# ESP32-with-USB.net
KiCad netlist of a schematic drawn in Altium Designer
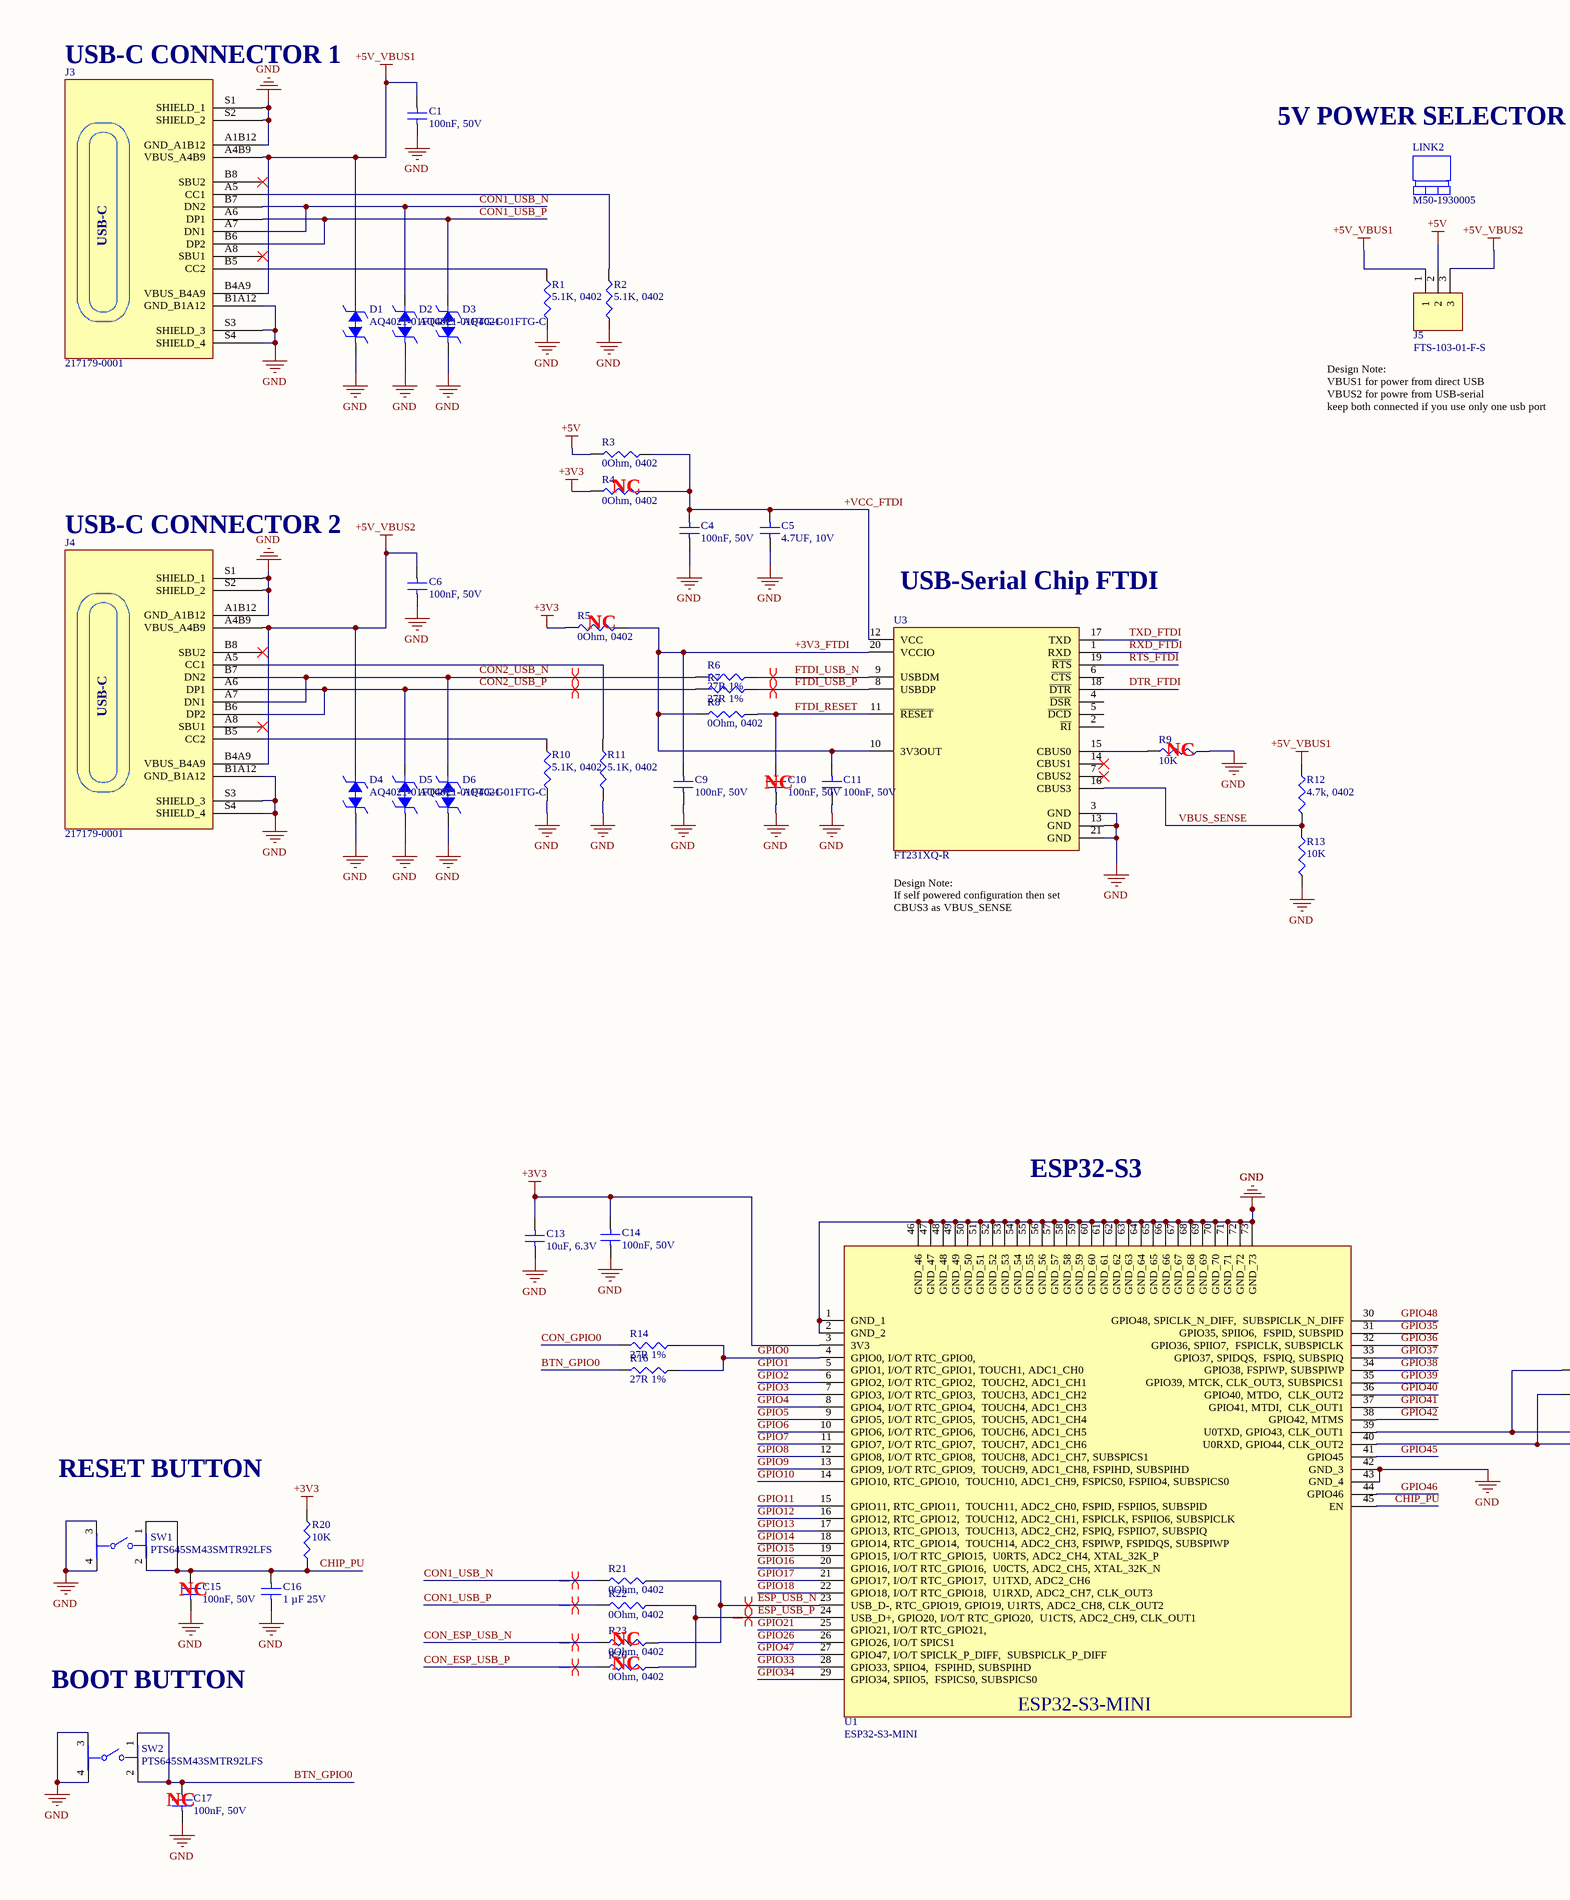
[diagram p0: ESP32-with-USB.SchDoc, left]
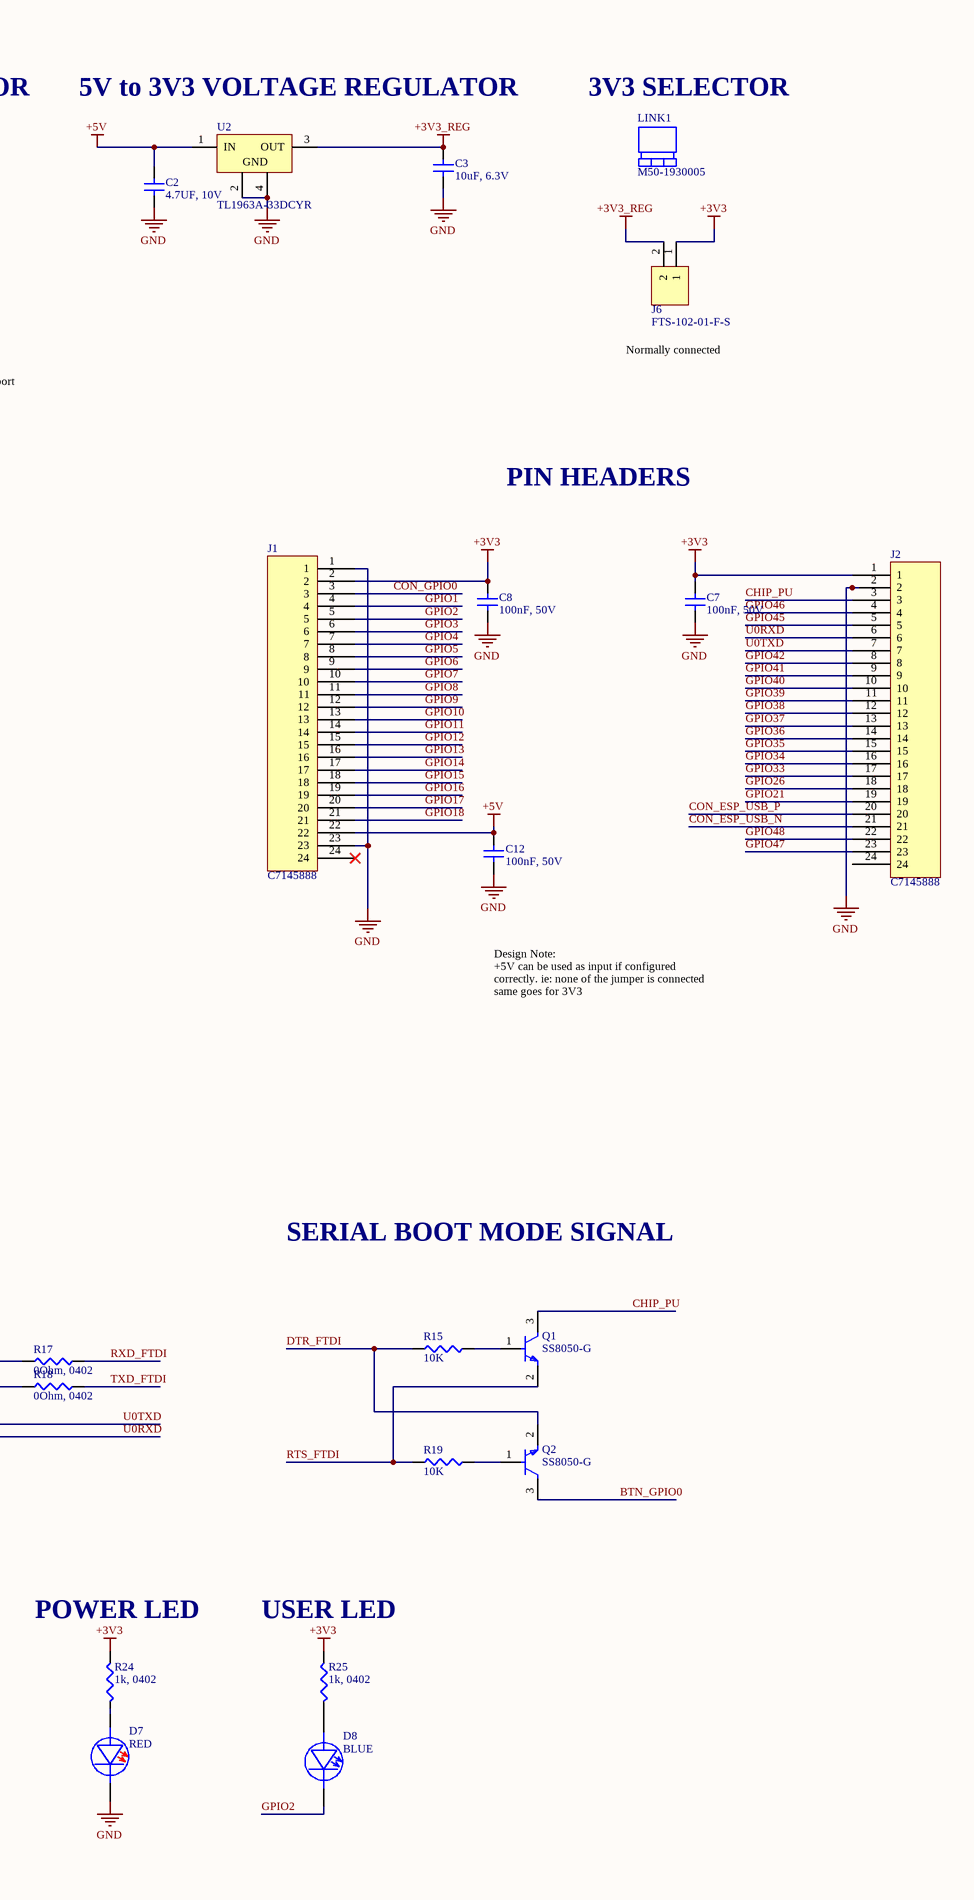
[diagram p1: ESP32-with-USB.SchDoc, right]

(export (version "E")
  (design (tool "Eeschema 10.0.6"))
  (components
    (comp (ref "C1")
      (value "100nF, 50V")
      (footprint "CAPC1005X55N")
      (description "0.1 µF ±10% 50V Ceramic Capacitor X7R 0402 (1005 Metric)")
      (fields
        (field (name "MANUFACTURER") "Samsung")
        (field (name "MANUFACTURER PART NUMBER") "CL05B104KB54PNC")
      )
      (libsource (lib "Schlib") (part "CL05B104KB54PNC"))
    )
    (comp (ref "C2")
      (value "4.7UF, 10V")
      (footprint "CAPC1005X55N")
      (description "CAP CER 4.7UF 10V X5R 0402")
      (fields
        (field (name "MANUFACTURER") "Samsung")
        (field (name "MANUFACTURER PART NUMBER") "CL05A475MP5NRNC")
      )
      (libsource (lib "Schlib") (part "CL05A475MP5NRNC"))
    )
    (comp (ref "C3")
      (value "10uF, 6.3V")
      (footprint "CAPC1005X55N")
      (description "10 µF ±20% 6.3V Ceramic Capacitor X5R 0402 (1005 Metric)")
      (fields
        (field (name "MANUFACTURER") "Murata")
        (field (name "MANUFACTURER PART NUMBER") "GRM155R60J106ME05D")
      )
      (libsource (lib "Schlib") (part "GRM155R60J106ME05D"))
    )
    (comp (ref "C4")
      (value "100nF, 50V")
      (footprint "CAPC1005X55N")
      (description "0.1 µF ±10% 50V Ceramic Capacitor X7R 0402 (1005 Metric)")
      (fields
        (field (name "MANUFACTURER") "Samsung")
        (field (name "MANUFACTURER PART NUMBER") "CL05B104KB54PNC")
      )
      (libsource (lib "Schlib") (part "CL05B104KB54PNC"))
    )
    (comp (ref "C5")
      (value "4.7UF, 10V")
      (footprint "CAPC1005X55N")
      (description "CAP CER 4.7UF 10V X5R 0402")
      (fields
        (field (name "MANUFACTURER") "Samsung")
        (field (name "MANUFACTURER PART NUMBER") "CL05A475MP5NRNC")
      )
      (libsource (lib "Schlib") (part "CL05A475MP5NRNC"))
    )
    (comp (ref "C6")
      (value "100nF, 50V")
      (footprint "CAPC1005X55N")
      (description "0.1 µF ±10% 50V Ceramic Capacitor X7R 0402 (1005 Metric)")
      (fields
        (field (name "MANUFACTURER") "Samsung")
        (field (name "MANUFACTURER PART NUMBER") "CL05B104KB54PNC")
      )
      (libsource (lib "Schlib") (part "CL05B104KB54PNC"))
    )
    (comp (ref "C7")
      (value "100nF, 50V")
      (footprint "CAPC1005X55N")
      (description "0.1 µF ±10% 50V Ceramic Capacitor X7R 0402 (1005 Metric)")
      (fields
        (field (name "MANUFACTURER") "Samsung")
        (field (name "MANUFACTURER PART NUMBER") "CL05B104KB54PNC")
      )
      (libsource (lib "Schlib") (part "CL05B104KB54PNC"))
    )
    (comp (ref "C8")
      (value "100nF, 50V")
      (footprint "CAPC1005X55N")
      (description "0.1 µF ±10% 50V Ceramic Capacitor X7R 0402 (1005 Metric)")
      (fields
        (field (name "MANUFACTURER") "Samsung")
        (field (name "MANUFACTURER PART NUMBER") "CL05B104KB54PNC")
      )
      (libsource (lib "Schlib") (part "CL05B104KB54PNC"))
    )
    (comp (ref "C9")
      (value "100nF, 50V")
      (footprint "CAPC1005X55N")
      (description "0.1 µF ±10% 50V Ceramic Capacitor X7R 0402 (1005 Metric)")
      (fields
        (field (name "MANUFACTURER") "Samsung")
        (field (name "MANUFACTURER PART NUMBER") "CL05B104KB54PNC")
      )
      (libsource (lib "Schlib") (part "CL05B104KB54PNC"))
    )
    (comp (ref "C10")
      (value "100nF, 50V")
      (footprint "CAPC1005X55N")
      (description "0.1 µF ±10% 50V Ceramic Capacitor X7R 0402 (1005 Metric)")
      (fields
        (field (name "MANUFACTURER") "Samsung")
        (field (name "MANUFACTURER PART NUMBER") "CL05B104KB54PNC")
      )
      (libsource (lib "Schlib") (part "CL05B104KB54PNC"))
    )
    (comp (ref "C11")
      (value "100nF, 50V")
      (footprint "CAPC1005X55N")
      (description "0.1 µF ±10% 50V Ceramic Capacitor X7R 0402 (1005 Metric)")
      (fields
        (field (name "MANUFACTURER") "Samsung")
        (field (name "MANUFACTURER PART NUMBER") "CL05B104KB54PNC")
      )
      (libsource (lib "Schlib") (part "CL05B104KB54PNC"))
    )
    (comp (ref "C12")
      (value "100nF, 50V")
      (footprint "CAPC1005X55N")
      (description "0.1 µF ±10% 50V Ceramic Capacitor X7R 0402 (1005 Metric)")
      (fields
        (field (name "MANUFACTURER") "Samsung")
        (field (name "MANUFACTURER PART NUMBER") "CL05B104KB54PNC")
      )
      (libsource (lib "Schlib") (part "CL05B104KB54PNC"))
    )
    (comp (ref "C13")
      (value "10uF, 6.3V")
      (footprint "CAPC1005X55N")
      (description "10 µF ±20% 6.3V Ceramic Capacitor X5R 0402 (1005 Metric)")
      (fields
        (field (name "MANUFACTURER") "Murata")
        (field (name "MANUFACTURER PART NUMBER") "GRM155R60J106ME05D")
      )
      (libsource (lib "Schlib") (part "GRM155R60J106ME05D"))
    )
    (comp (ref "C14")
      (value "100nF, 50V")
      (footprint "CAPC1005X55N")
      (description "0.1 µF ±10% 50V Ceramic Capacitor X7R 0402 (1005 Metric)")
      (fields
        (field (name "MANUFACTURER") "Samsung")
        (field (name "MANUFACTURER PART NUMBER") "CL05B104KB54PNC")
      )
      (libsource (lib "Schlib") (part "CL05B104KB54PNC"))
    )
    (comp (ref "C15")
      (value "100nF, 50V")
      (footprint "CAPC1005X55N")
      (description "0.1 µF ±10% 50V Ceramic Capacitor X7R 0402 (1005 Metric)")
      (fields
        (field (name "MANUFACTURER") "Samsung")
        (field (name "MANUFACTURER PART NUMBER") "CL05B104KB54PNC")
      )
      (libsource (lib "Schlib") (part "CL05B104KB54PNC"))
    )
    (comp (ref "C16")
      (value "1 µF 25V")
      (footprint "CAPC1005X55N")
      (description "1 µF ±10% 25V Ceramic Capacitor X5R 0402 (1005 Metric)")
      (fields
        (field (name "MANUFACTURER") "Samsung")
        (field (name "MANUFACTURER PART NUMBER") "CL05A105KA5NQNC")
      )
      (libsource (lib "Schlib") (part "CL05A105KA5NQNC"))
    )
    (comp (ref "C17")
      (value "100nF, 50V")
      (footprint "CAPC1005X55N")
      (description "0.1 µF ±10% 50V Ceramic Capacitor X7R 0402 (1005 Metric)")
      (fields
        (field (name "MANUFACTURER") "Samsung")
        (field (name "MANUFACTURER PART NUMBER") "CL05B104KB54PNC")
      )
      (libsource (lib "Schlib") (part "CL05B104KB54PNC"))
    )
    (comp (ref "D1")
      (value "AQ4021-01FTG-C")
      (footprint "AQ4021-01FTG-C_0805")
      (description "Trans Voltage Suppressor Diode")
      (fields (field (name "MANUFACTURER") "Littelfuse") (field (name "LCSC PART NUMBER") "C708873"))
      (libsource (lib "Schlib") (part "AQ4021-01FTG-C"))
    )
    (comp (ref "D2")
      (value "AQ4021-01FTG-C")
      (footprint "AQ4021-01FTG-C_0805")
      (description "Trans Voltage Suppressor Diode")
      (fields (field (name "MANUFACTURER") "Littelfuse") (field (name "LCSC PART NUMBER") "C708873"))
      (libsource (lib "Schlib") (part "AQ4021-01FTG-C"))
    )
    (comp (ref "D3")
      (value "AQ4021-01FTG-C")
      (footprint "AQ4021-01FTG-C_0805")
      (description "Trans Voltage Suppressor Diode")
      (fields (field (name "MANUFACTURER") "Littelfuse") (field (name "LCSC PART NUMBER") "C708873"))
      (libsource (lib "Schlib") (part "AQ4021-01FTG-C"))
    )
    (comp (ref "D4")
      (value "AQ4021-01FTG-C")
      (footprint "AQ4021-01FTG-C_0805")
      (description "Trans Voltage Suppressor Diode")
      (fields (field (name "MANUFACTURER") "Littelfuse") (field (name "LCSC PART NUMBER") "C708873"))
      (libsource (lib "Schlib") (part "AQ4021-01FTG-C"))
    )
    (comp (ref "D5")
      (value "AQ4021-01FTG-C")
      (footprint "AQ4021-01FTG-C_0805")
      (description "Trans Voltage Suppressor Diode")
      (fields (field (name "MANUFACTURER") "Littelfuse") (field (name "LCSC PART NUMBER") "C708873"))
      (libsource (lib "Schlib") (part "AQ4021-01FTG-C"))
    )
    (comp (ref "D6")
      (value "AQ4021-01FTG-C")
      (footprint "AQ4021-01FTG-C_0805")
      (description "Trans Voltage Suppressor Diode")
      (fields (field (name "MANUFACTURER") "Littelfuse") (field (name "LCSC PART NUMBER") "C708873"))
      (libsource (lib "Schlib") (part "AQ4021-01FTG-C"))
    )
    (comp (ref "D7")
      (value "RED")
      (footprint "LED_RED_0402")
      (description "LED RED 0402 SMD")
      (fields
        (field (name "MANUFACTURER") "Vishay")
        (field (name "MANUFACTURER PART NUMBER") "VLMS1500-GS08")
      )
      (libsource (lib "Schlib") (part "VLMS1500-GS08"))
    )
    (comp (ref "D8")
      (value "BLUE")
      (footprint "LED_BLUE_0402")
      (description "LED BLUE 0402 SMD 468nm")
      (fields
        (field (name "MANUFACTURER") "Vishay")
        (field (name "MANUFACTURER PART NUMBER") "VLMB1500-GS08")
      )
      (libsource (lib "Schlib") (part "VLMB1500-GS08"))
    )
    (comp (ref "J1")
      (value "C7145888")
      (footprint "HDR_1X24_2.54MM")
      (description "CONN HEADER VERT 24POS 2.54MM")
      (fields (field (name "MANUFACTURER") "Molex") (field (name "MANUFACTURER PART NUMBER") "0022284245"))
      (libsource (lib "Schlib") (part "0022284245"))
    )
    (comp (ref "J2")
      (value "C7145888")
      (footprint "HDR_1X24_2.54MM")
      (description "CONN HEADER VERT 24POS 2.54MM")
      (fields (field (name "MANUFACTURER") "Molex") (field (name "MANUFACTURER PART NUMBER") "0022284245"))
      (libsource (lib "") (part "0022284245_1"))
    )
    (comp (ref "J3")
      (value "217179-0001")
      (footprint "FP-2171790001-MFG")
      (description "USB Type C - Connector, Top-mount SMT, 16pos ¦ Molex Incorporated 217179-0001")
      (fields (field (name "MANUFACTURER") "Molex") (field (name "LCSC PART NUMBER") "C3197684"))
      (libsource (lib "Schlib") (part "217179-0001"))
    )
    (comp (ref "J4")
      (value "217179-0001")
      (footprint "FP-2171790001-MFG")
      (description "USB Type C - Connector, Top-mount SMT, 16pos ¦ Molex Incorporated 217179-0001")
      (fields (field (name "MANUFACTURER") "Molex") (field (name "LCSC PART NUMBER") "C3197684"))
      (libsource (lib "Schlib") (part "217179-0001"))
    )
    (comp (ref "J5")
      (value "FTS-103-01-F-S")
      (footprint "HDR_1X3_1.27MM")
      (description "CONN HEADER VERT 3POS 1.27MM")
      (fields (field (name "MANUFACTURER") "Samtec") (field (name "LCSC PART NUMBER") "C3333578"))
      (libsource (lib "Schlib") (part "FTS-103-01-F-S"))
    )
    (comp (ref "J6")
      (value "FTS-102-01-F-S")
      (footprint "HDR_1X2_1.27MM")
      (description "CONN HEADER VERT 2POS 1.27MM")
      (fields (field (name "MANUFACTURER") "Samtec") (field (name "LCSC PART NUMBER") "C6045317"))
      (libsource (lib "Schlib") (part "FTS-102-01-F-S"))
    )
    (comp (ref "LINK1")
      (value "M50-1930005")
      (description "CONN SHUNT 1.27MM BLUE")
      (fields (field (name "MANUFACTURER") "Harwin") (field (name "LCSC PART NUMBER") "C6586863"))
      (libsource (lib "Schlib") (part "M50-1930005"))
    )
    (comp (ref "LINK2")
      (value "M50-1930005")
      (description "CONN SHUNT 1.27MM BLUE")
      (fields (field (name "MANUFACTURER") "Harwin") (field (name "LCSC PART NUMBER") "C6586863"))
      (libsource (lib "Schlib") (part "M50-1930005"))
    )
    (comp (ref "Q1")
      (value "SS8050-G")
      (footprint "FP-SS8050-G-IPC_B")
      (description "TRANS NPN 25V 1.5A SOT23-3")
      (fields (field (name "MANUFACTURER") "Comchip") (field (name "LCSC PART NUMBER") "C164886"))
      (libsource (lib "Schlib") (part "SS8050-G"))
    )
    (comp (ref "Q2")
      (value "SS8050-G")
      (footprint "FP-SS8050-G-IPC_B")
      (description "TRANS NPN 25V 1.5A SOT23-3")
      (fields (field (name "MANUFACTURER") "Comchip") (field (name "LCSC PART NUMBER") "C164886"))
      (libsource (lib "Schlib") (part "SS8050-G"))
    )
    (comp (ref "R1")
      (value "5.1K, 0402")
      (footprint "RESC1005X37N")
      (description "5.1kOhm 1% 1/16W 0402")
      (fields
        (field (name "MANUFACTURER") "Yageo")
        (field (name "MANUFACTURER PART NUMBER") "RC0402FR-075K1L")
      )
      (libsource (lib "Schlib") (part "RC0402FR-075K1L"))
    )
    (comp (ref "R2")
      (value "5.1K, 0402")
      (footprint "RESC1005X37N")
      (description "5.1kOhm 1% 1/16W 0402")
      (fields
        (field (name "MANUFACTURER") "Yageo")
        (field (name "MANUFACTURER PART NUMBER") "RC0402FR-075K1L")
      )
      (libsource (lib "Schlib") (part "RC0402FR-075K1L"))
    )
    (comp (ref "R3")
      (value "0Ohm, 0402")
      (footprint "RESC1005X37N")
      (description "RES 0 OHM JUMPER 1/16W 0402")
      (fields
        (field (name "MANUFACTURER") "Yageo")
        (field (name "MANUFACTURER PART NUMBER") "RC0402JR-070RL")
      )
      (libsource (lib "Schlib") (part "RC0402JR-070RL"))
    )
    (comp (ref "R4")
      (value "0Ohm, 0402")
      (footprint "RESC1005X37N")
      (description "RES 0 OHM JUMPER 1/16W 0402")
      (fields
        (field (name "MANUFACTURER") "Yageo")
        (field (name "MANUFACTURER PART NUMBER") "RC0402JR-070RL")
      )
      (libsource (lib "Schlib") (part "RC0402JR-070RL"))
    )
    (comp (ref "R5")
      (value "0Ohm, 0402")
      (footprint "RESC1005X37N")
      (description "RES 0 OHM JUMPER 1/16W 0402")
      (fields
        (field (name "MANUFACTURER") "Yageo")
        (field (name "MANUFACTURER PART NUMBER") "RC0402JR-070RL")
      )
      (libsource (lib "Schlib") (part "RC0402JR-070RL"))
    )
    (comp (ref "R6")
      (value "27R 1%")
      (footprint "RESC1005X37N")
      (description "27 OHM 1% 1/16W 0402")
      (fields
        (field (name "MANUFACTURER") "Yageo")
        (field (name "MANUFACTURER PART NUMBER") "RC0402FR-0727RL")
      )
      (libsource (lib "Schlib") (part "RC0402FR-0727RL"))
    )
    (comp (ref "R7")
      (value "27R 1%")
      (footprint "RESC1005X37N")
      (description "27 OHM 1% 1/16W 0402")
      (fields
        (field (name "MANUFACTURER") "Yageo")
        (field (name "MANUFACTURER PART NUMBER") "RC0402FR-0727RL")
      )
      (libsource (lib "Schlib") (part "RC0402FR-0727RL"))
    )
    (comp (ref "R8")
      (value "0Ohm, 0402")
      (footprint "RESC1005X37N")
      (description "RES 0 OHM JUMPER 1/16W 0402")
      (fields
        (field (name "MANUFACTURER") "Yageo")
        (field (name "MANUFACTURER PART NUMBER") "RC0402JR-070RL")
      )
      (libsource (lib "Schlib") (part "RC0402JR-070RL"))
    )
    (comp (ref "R9")
      (value "10K")
      (footprint "RESC1005X37N")
      (description "10 kOhm, ± 1%, 62.5 mW, 0402 [1005 Metric], SMD Chip Resistor, Thick Film, General Purpose")
      (fields
        (field (name "MANUFACTURER") "Yageo")
        (field (name "MANUFACTURER PART NUMBER") "AC0402FR-0710KL")
      )
      (libsource (lib "Schlib") (part "AC0402FR-0710KL"))
    )
    (comp (ref "R10")
      (value "5.1K, 0402")
      (footprint "RESC1005X37N")
      (description "5.1kOhm 1% 1/16W 0402")
      (fields
        (field (name "MANUFACTURER") "Yageo")
        (field (name "MANUFACTURER PART NUMBER") "RC0402FR-075K1L")
      )
      (libsource (lib "Schlib") (part "RC0402FR-075K1L"))
    )
    (comp (ref "R11")
      (value "5.1K, 0402")
      (footprint "RESC1005X37N")
      (description "5.1kOhm 1% 1/16W 0402")
      (fields
        (field (name "MANUFACTURER") "Yageo")
        (field (name "MANUFACTURER PART NUMBER") "RC0402FR-075K1L")
      )
      (libsource (lib "Schlib") (part "RC0402FR-075K1L"))
    )
    (comp (ref "R12")
      (value "4.7k, 0402")
      (footprint "RESC1005X37N")
      (description "RES 4.7K OHM 1% 1/16W 0402")
      (fields
        (field (name "MANUFACTURER") "Yageo")
        (field (name "MANUFACTURER PART NUMBER") "RC0402FR-074K7L")
      )
      (libsource (lib "Schlib") (part "RC0402FR-074K7L"))
    )
    (comp (ref "R13")
      (value "10K")
      (footprint "RESC1005X37N")
      (description "10 kOhm, ± 1%, 62.5 mW, 0402 [1005 Metric], SMD Chip Resistor, Thick Film, General Purpose")
      (fields
        (field (name "MANUFACTURER") "Yageo")
        (field (name "MANUFACTURER PART NUMBER") "AC0402FR-0710KL")
      )
      (libsource (lib "Schlib") (part "AC0402FR-0710KL"))
    )
    (comp (ref "R14")
      (value "27R 1%")
      (footprint "RESC1005X37N")
      (description "27 OHM 1% 1/16W 0402")
      (fields
        (field (name "MANUFACTURER") "Yageo")
        (field (name "MANUFACTURER PART NUMBER") "RC0402FR-0727RL")
      )
      (libsource (lib "Schlib") (part "RC0402FR-0727RL"))
    )
    (comp (ref "R15")
      (value "10K")
      (footprint "RESC1005X37N")
      (description "10 kOhm, ± 1%, 62.5 mW, 0402 [1005 Metric], SMD Chip Resistor, Thick Film, General Purpose")
      (fields
        (field (name "MANUFACTURER") "Yageo")
        (field (name "MANUFACTURER PART NUMBER") "AC0402FR-0710KL")
      )
      (libsource (lib "Schlib") (part "AC0402FR-0710KL"))
    )
    (comp (ref "R16")
      (value "27R 1%")
      (footprint "RESC1005X37N")
      (description "27 OHM 1% 1/16W 0402")
      (fields
        (field (name "MANUFACTURER") "Yageo")
        (field (name "MANUFACTURER PART NUMBER") "RC0402FR-0727RL")
      )
      (libsource (lib "Schlib") (part "RC0402FR-0727RL"))
    )
    (comp (ref "R17")
      (value "0Ohm, 0402")
      (footprint "RESC1005X37N")
      (description "RES 0 OHM JUMPER 1/16W 0402")
      (fields
        (field (name "MANUFACTURER") "Yageo")
        (field (name "MANUFACTURER PART NUMBER") "RC0402JR-070RL")
      )
      (libsource (lib "Schlib") (part "RC0402JR-070RL"))
    )
    (comp (ref "R18")
      (value "0Ohm, 0402")
      (footprint "RESC1005X37N")
      (description "RES 0 OHM JUMPER 1/16W 0402")
      (fields
        (field (name "MANUFACTURER") "Yageo")
        (field (name "MANUFACTURER PART NUMBER") "RC0402JR-070RL")
      )
      (libsource (lib "Schlib") (part "RC0402JR-070RL"))
    )
    (comp (ref "R19")
      (value "10K")
      (footprint "RESC1005X37N")
      (description "10 kOhm, ± 1%, 62.5 mW, 0402 [1005 Metric], SMD Chip Resistor, Thick Film, General Purpose")
      (fields
        (field (name "MANUFACTURER") "Yageo")
        (field (name "MANUFACTURER PART NUMBER") "AC0402FR-0710KL")
      )
      (libsource (lib "Schlib") (part "AC0402FR-0710KL"))
    )
    (comp (ref "R20")
      (value "10K")
      (footprint "RESC1005X37N")
      (description "10 kOhm, ± 1%, 62.5 mW, 0402 [1005 Metric], SMD Chip Resistor, Thick Film, General Purpose")
      (fields
        (field (name "MANUFACTURER") "Yageo")
        (field (name "MANUFACTURER PART NUMBER") "AC0402FR-0710KL")
      )
      (libsource (lib "Schlib") (part "AC0402FR-0710KL"))
    )
    (comp (ref "R21")
      (value "0Ohm, 0402")
      (footprint "RESC1005X37N")
      (description "RES 0 OHM JUMPER 1/16W 0402")
      (fields
        (field (name "MANUFACTURER") "Yageo")
        (field (name "MANUFACTURER PART NUMBER") "RC0402JR-070RL")
      )
      (libsource (lib "Schlib") (part "RC0402JR-070RL"))
    )
    (comp (ref "R22")
      (value "0Ohm, 0402")
      (footprint "RESC1005X37N")
      (description "RES 0 OHM JUMPER 1/16W 0402")
      (fields
        (field (name "MANUFACTURER") "Yageo")
        (field (name "MANUFACTURER PART NUMBER") "RC0402JR-070RL")
      )
      (libsource (lib "Schlib") (part "RC0402JR-070RL"))
    )
    (comp (ref "R23")
      (value "0Ohm, 0402")
      (footprint "RESC1005X37N")
      (description "RES 0 OHM JUMPER 1/16W 0402")
      (fields
        (field (name "MANUFACTURER") "Yageo")
        (field (name "MANUFACTURER PART NUMBER") "RC0402JR-070RL")
      )
      (libsource (lib "Schlib") (part "RC0402JR-070RL"))
    )
    (comp (ref "R24")
      (value "1k, 0402")
      (footprint "RESC1005X37N")
      (description "RES 1K OHM 1% 1/16W 0402")
      (fields
        (field (name "MANUFACTURER") "Yageo")
        (field (name "MANUFACTURER PART NUMBER") "RC0402FR-071KL")
      )
      (libsource (lib "Schlib") (part "RC0402FR-071KL"))
    )
    (comp (ref "R25")
      (value "1k, 0402")
      (footprint "RESC1005X37N")
      (description "RES 1K OHM 1% 1/16W 0402")
      (fields
        (field (name "MANUFACTURER") "Yageo")
        (field (name "MANUFACTURER PART NUMBER") "RC0402FR-071KL")
      )
      (libsource (lib "Schlib") (part "RC0402FR-071KL"))
    )
    (comp (ref "R26")
      (value "0Ohm, 0402")
      (footprint "RESC1005X37N")
      (description "RES 0 OHM JUMPER 1/16W 0402")
      (fields
        (field (name "MANUFACTURER") "Yageo")
        (field (name "MANUFACTURER PART NUMBER") "RC0402JR-070RL")
      )
      (libsource (lib "Schlib") (part "RC0402JR-070RL"))
    )
    (comp (ref "SW1")
      (value "PTS645SM43SMTR92LFS")
      (footprint "FP-PTS645SM43SMTR92LFS-MFG")
      (description "SWITCH TACTILE SPST-NO 0.05A 12V")
      (fields (field (name "MANUFACTURER") "ITT C&K") (field (name "LCSC PART NUMBER") "C221880"))
      (libsource (lib "Schlib") (part "PTS645SM43SMTR92LFS"))
    )
    (comp (ref "SW2")
      (value "PTS645SM43SMTR92LFS")
      (footprint "FP-PTS645SM43SMTR92LFS-MFG")
      (description "SWITCH TACTILE SPST-NO 0.05A 12V")
      (fields (field (name "MANUFACTURER") "ITT C&K") (field (name "LCSC PART NUMBER") "C221880"))
      (libsource (lib "Schlib") (part "PTS645SM43SMTR92LFS"))
    )
    (comp (ref "U1")
      (value "ESP32-S3-MINI")
      (footprint "XCVR_ESP32-S3-MINI-1-N8")
      (description "ESP32-S3FN8, 8 MB SPI flash, PCB antenna")
      (fields
        (field (name "MANUFACTURER") "Espressif Systems")
        (field (name "MANUFACTURER PART NUMBER") "ESP32-S3-MINI-1-N8")
      )
      (libsource (lib "Schlib") (part "ESP32-S3-MINI-1-N8"))
    )
    (comp (ref "U2")
      (value "TL1963A-33DCYR")
      (footprint "DCY0004A_N")
      (description "IC REG LINEAR 3.3V 1.5A SOT223-4")
      (fields (field (name "MANUFACTURER") "Texas Instruments") (field (name "LCSC PART NUMBER") "C181262"))
      (libsource (lib "Schlib") (part "TL1963A-33DCYR"))
    )
    (comp (ref "U3")
      (value "FT231XQ-R")
      (footprint "FP-QFN-20-IPC_B")
      (description "IC USB SERIAL FULL UART 20QFN")
      (fields (field (name "MANUFACTURER") "FTDI") (field (name "LCSC PART NUMBER") "C132159"))
      (libsource (lib "Schlib") (part "FT231XQ-R"))
    )
  )
  (nets
    (net (code "1") (name "+3V3") (class "Default")
      (node (ref "C13") (pin "2") (pinfunction "2_2") (pintype "passive"))
      (node (ref "C14") (pin "2") (pinfunction "2_2") (pintype "passive"))
      (node (ref "C7") (pin "2") (pinfunction "2_2") (pintype "passive"))
      (node (ref "C8") (pin "2") (pinfunction "2_2") (pintype "passive"))
      (node (ref "J1") (pin "2") (pinfunction "2_2") (pintype "passive"))
      (node (ref "J2") (pin "1") (pinfunction "1_1") (pintype "passive"))
      (node (ref "J6") (pin "1") (pinfunction "1_1") (pintype "passive"))
      (node (ref "R20") (pin "2") (pinfunction "2_2") (pintype "passive"))
      (node (ref "R24") (pin "1") (pinfunction "1_1") (pintype "passive"))
      (node (ref "R25") (pin "1") (pinfunction "1_1") (pintype "passive"))
      (node (ref "R4") (pin "1") (pinfunction "1_1") (pintype "passive"))
      (node (ref "R5") (pin "1") (pinfunction "1_1") (pintype "passive"))
      (node (ref "U1") (pin "3") (pinfunction "3V3_3") (pintype "passive"))
    )
    (net (code "2") (name "+3V3_REG") (class "Default")
      (node (ref "C3") (pin "2") (pinfunction "2_2") (pintype "passive"))
      (node (ref "J6") (pin "2") (pinfunction "2_2") (pintype "passive"))
      (node (ref "U2") (pin "3") (pinfunction "OUT_3") (pintype "power_in"))
    )
    (net (code "3") (name "+5V") (class "Default")
      (node (ref "C12") (pin "2") (pinfunction "2_2") (pintype "passive"))
      (node (ref "C2") (pin "2") (pinfunction "2_2") (pintype "passive"))
      (node (ref "J1") (pin "22") (pinfunction "22_22") (pintype "passive"))
      (node (ref "J5") (pin "2") (pinfunction "2_2") (pintype "passive"))
      (node (ref "R3") (pin "1") (pinfunction "1_1") (pintype "passive"))
      (node (ref "U2") (pin "1") (pinfunction "IN_1") (pintype "power_in"))
    )
    (net (code "4") (name "+5V_VBUS1") (class "Default")
      (node (ref "C1") (pin "2") (pinfunction "2_2") (pintype "passive"))
      (node (ref "D1") (pin "2") (pinfunction "2_2") (pintype "passive"))
      (node (ref "J3") (pin "A4B9") (pinfunction "VBUS_A4B9_A4B9") (pintype "passive"))
      (node (ref "J3") (pin "B4A9") (pinfunction "VBUS_B4A9_B4A9") (pintype "passive"))
      (node (ref "J5") (pin "1") (pinfunction "1_1") (pintype "passive"))
      (node (ref "R12") (pin "2") (pinfunction "2_2") (pintype "passive"))
    )
    (net (code "5") (name "+5V_VBUS2") (class "Default")
      (node (ref "C6") (pin "2") (pinfunction "2_2") (pintype "passive"))
      (node (ref "D4") (pin "2") (pinfunction "2_2") (pintype "passive"))
      (node (ref "J4") (pin "A4B9") (pinfunction "VBUS_A4B9_A4B9") (pintype "passive"))
      (node (ref "J4") (pin "B4A9") (pinfunction "VBUS_B4A9_B4A9") (pintype "passive"))
      (node (ref "J5") (pin "3") (pinfunction "3_3") (pintype "passive"))
    )
    (net (code "6") (name "/+3V3_FTDI") (class "Default")
      (node (ref "C11") (pin "2") (pinfunction "2_2") (pintype "passive"))
      (node (ref "C9") (pin "2") (pinfunction "2_2") (pintype "passive"))
      (node (ref "R5") (pin "2") (pinfunction "2_2") (pintype "passive"))
      (node (ref "R8") (pin "1") (pinfunction "1_1") (pintype "passive"))
      (node (ref "U3") (pin "10") (pinfunction "3V3OUT_10") (pintype "passive"))
      (node (ref "U3") (pin "20") (pinfunction "VCCIO_20") (pintype "passive"))
    )
    (net (code "7") (name "/+VCC_FTDI") (class "Default")
      (node (ref "C4") (pin "2") (pinfunction "2_2") (pintype "passive"))
      (node (ref "C5") (pin "2") (pinfunction "2_2") (pintype "passive"))
      (node (ref "R3") (pin "2") (pinfunction "2_2") (pintype "passive"))
      (node (ref "R4") (pin "2") (pinfunction "2_2") (pintype "passive"))
      (node (ref "U3") (pin "12") (pinfunction "VCC_12") (pintype "passive"))
    )
    (net (code "8") (name "/BTN_GPIO0") (class "Default")
      (node (ref "C17") (pin "2") (pinfunction "2_2") (pintype "passive"))
      (node (ref "Q2") (pin "3") (pinfunction "C_3") (pintype "passive"))
      (node (ref "R16") (pin "1") (pinfunction "1_1") (pintype "passive"))
      (node (ref "SW2") (pin "1") (pinfunction "1_1") (pintype "passive"))
      (node (ref "SW2") (pin "2") (pinfunction "2_2") (pintype "passive"))
    )
    (net (code "9") (name "/CHIP_PU") (class "Default")
      (node (ref "C15") (pin "2") (pinfunction "2_2") (pintype "passive"))
      (node (ref "C16") (pin "2") (pinfunction "2_2") (pintype "passive"))
      (node (ref "J2") (pin "3") (pinfunction "3_3") (pintype "passive"))
      (node (ref "Q1") (pin "3") (pinfunction "C_3") (pintype "passive"))
      (node (ref "R20") (pin "1") (pinfunction "1_1") (pintype "passive"))
      (node (ref "SW1") (pin "1") (pinfunction "1_1") (pintype "passive"))
      (node (ref "SW1") (pin "2") (pinfunction "2_2") (pintype "passive"))
      (node (ref "U1") (pin "45") (pinfunction "EN_45") (pintype "passive"))
    )
    (net (code "10") (name "/CON1_USB_N") (class "Default")
      (node (ref "D2") (pin "2") (pinfunction "2_2") (pintype "passive"))
      (node (ref "J3") (pin "A7") (pinfunction "DN1_A7") (pintype "passive"))
      (node (ref "J3") (pin "B7") (pinfunction "DN2_B7") (pintype "passive"))
      (node (ref "R21") (pin "1") (pinfunction "1_1") (pintype "passive"))
    )
    (net (code "11") (name "/CON1_USB_P") (class "Default")
      (node (ref "D3") (pin "2") (pinfunction "2_2") (pintype "passive"))
      (node (ref "J3") (pin "A6") (pinfunction "DP1_A6") (pintype "passive"))
      (node (ref "J3") (pin "B6") (pinfunction "DP2_B6") (pintype "passive"))
      (node (ref "R22") (pin "1") (pinfunction "1_1") (pintype "passive"))
    )
    (net (code "12") (name "/CON2_USB_N") (class "Default")
      (node (ref "D6") (pin "2") (pinfunction "2_2") (pintype "passive"))
      (node (ref "J4") (pin "A7") (pinfunction "DN1_A7") (pintype "passive"))
      (node (ref "J4") (pin "B7") (pinfunction "DN2_B7") (pintype "passive"))
      (node (ref "R6") (pin "1") (pinfunction "1_1") (pintype "passive"))
    )
    (net (code "13") (name "/CON2_USB_P") (class "Default")
      (node (ref "D5") (pin "2") (pinfunction "2_2") (pintype "passive"))
      (node (ref "J4") (pin "A6") (pinfunction "DP1_A6") (pintype "passive"))
      (node (ref "J4") (pin "B6") (pinfunction "DP2_B6") (pintype "passive"))
      (node (ref "R7") (pin "1") (pinfunction "1_1") (pintype "passive"))
    )
    (net (code "14") (name "/CON_ESP_USB_N") (class "Default")
      (node (ref "J2") (pin "21") (pinfunction "21_21") (pintype "passive"))
      (node (ref "R23") (pin "1") (pinfunction "1_1") (pintype "passive"))
    )
    (net (code "15") (name "/CON_ESP_USB_P") (class "Default")
      (node (ref "J2") (pin "20") (pinfunction "20_20") (pintype "passive"))
      (node (ref "R26") (pin "1") (pinfunction "1_1") (pintype "passive"))
    )
    (net (code "16") (name "/CON_GPIO0") (class "Default")
      (node (ref "J1") (pin "3") (pinfunction "3_3") (pintype "passive"))
      (node (ref "R14") (pin "1") (pinfunction "1_1") (pintype "passive"))
    )
    (net (code "17") (name "/DTR_FTDI") (class "Default")
      (node (ref "Q2") (pin "2") (pinfunction "E_2") (pintype "passive"))
      (node (ref "R15") (pin "1") (pinfunction "1_1") (pintype "passive"))
      (node (ref "U3") (pin "18") (pinfunction "~{DTR}_18") (pintype "passive"))
    )
    (net (code "18") (name "/ESP_USB_N") (class "Default")
      (node (ref "R21") (pin "2") (pinfunction "2_2") (pintype "passive"))
      (node (ref "R23") (pin "2") (pinfunction "2_2") (pintype "passive"))
      (node (ref "U1") (pin "23") (pinfunction "USB_D-,_RTC_GPIO19,_GPIO19,_U1RTS,_ADC2_CH8,_CLK_OUT2_23") (pintype "passive"))
    )
    (net (code "19") (name "/ESP_USB_P") (class "Default")
      (node (ref "R22") (pin "2") (pinfunction "2_2") (pintype "passive"))
      (node (ref "R26") (pin "2") (pinfunction "2_2") (pintype "passive"))
      (node (ref "U1") (pin "24") (pinfunction "USB_D+,_GPIO20,_I/O/T_RTC_GPIO20,__U1CTS,_ADC2_CH9,_CLK_OUT1_24") (pintype "passive"))
    )
    (net (code "20") (name "/FTDI_RESET") (class "Default")
      (node (ref "C10") (pin "2") (pinfunction "2_2") (pintype "passive"))
      (node (ref "R8") (pin "2") (pinfunction "2_2") (pintype "passive"))
      (node (ref "U3") (pin "11") (pinfunction "~{RESET}_11") (pintype "passive"))
    )
    (net (code "21") (name "/FTDI_USB_N") (class "Default")
      (node (ref "R6") (pin "2") (pinfunction "2_2") (pintype "passive"))
      (node (ref "U3") (pin "9") (pinfunction "USBDM_9") (pintype "passive"))
    )
    (net (code "22") (name "/FTDI_USB_P") (class "Default")
      (node (ref "R7") (pin "2") (pinfunction "2_2") (pintype "passive"))
      (node (ref "U3") (pin "8") (pinfunction "USBDP_8") (pintype "passive"))
    )
    (net (code "23") (name "/GPIO0") (class "Default")
      (node (ref "R14") (pin "2") (pinfunction "2_2") (pintype "passive"))
      (node (ref "R16") (pin "2") (pinfunction "2_2") (pintype "passive"))
      (node (ref "U1") (pin "4") (pinfunction "GPIO0,_I/O/T_RTC_GPIO0,_4") (pintype "passive"))
    )
    (net (code "24") (name "/GPIO1") (class "Default")
      (node (ref "J1") (pin "4") (pinfunction "4_4") (pintype "passive"))
      (node (ref "U1") (pin "5") (pinfunction "GPIO1,_I/O/T_RTC_GPIO1,_TOUCH1,_ADC1_CH0_5") (pintype "passive"))
    )
    (net (code "25") (name "/GPIO2") (class "Default")
      (node (ref "D8") (pin "K-") (pinfunction "2_K-") (pintype "passive"))
      (node (ref "J1") (pin "5") (pinfunction "5_5") (pintype "passive"))
      (node (ref "U1") (pin "6") (pinfunction "GPIO2,_I/O/T_RTC_GPIO2,__TOUCH2,_ADC1_CH1_6") (pintype "passive"))
    )
    (net (code "26") (name "/GPIO3") (class "Default")
      (node (ref "J1") (pin "6") (pinfunction "6_6") (pintype "passive"))
      (node (ref "U1") (pin "7") (pinfunction "GPIO3,_I/O/T_RTC_GPIO3,__TOUCH3,_ADC1_CH2_7") (pintype "passive"))
    )
    (net (code "27") (name "/GPIO4") (class "Default")
      (node (ref "J1") (pin "7") (pinfunction "7_7") (pintype "passive"))
      (node (ref "U1") (pin "8") (pinfunction "GPIO4,_I/O/T_RTC_GPIO4,__TOUCH4,_ADC1_CH3_8") (pintype "passive"))
    )
    (net (code "28") (name "/GPIO5") (class "Default")
      (node (ref "J1") (pin "8") (pinfunction "8_8") (pintype "passive"))
      (node (ref "U1") (pin "9") (pinfunction "GPIO5,_I/O/T_RTC_GPIO5,__TOUCH5,_ADC1_CH4_9") (pintype "passive"))
    )
    (net (code "29") (name "/GPIO6") (class "Default")
      (node (ref "J1") (pin "9") (pinfunction "9_9") (pintype "passive"))
      (node (ref "U1") (pin "10") (pinfunction "GPIO6,_I/O/T_RTC_GPIO6,__TOUCH6,_ADC1_CH5_10") (pintype "passive"))
    )
    (net (code "30") (name "/GPIO7") (class "Default")
      (node (ref "J1") (pin "10") (pinfunction "10_10") (pintype "passive"))
      (node (ref "U1") (pin "11") (pinfunction "GPIO7,_I/O/T_RTC_GPIO7,__TOUCH7,_ADC1_CH6_11") (pintype "passive"))
    )
    (net (code "31") (name "/GPIO8") (class "Default")
      (node (ref "J1") (pin "11") (pinfunction "11_11") (pintype "passive"))
      (node (ref "U1") (pin "12") (pinfunction "GPIO8,_I/O/T_RTC_GPIO8,__TOUCH8,_ADC1_CH7,_SUBSPICS1_12") (pintype "passive"))
    )
    (net (code "32") (name "/GPIO9") (class "Default")
      (node (ref "J1") (pin "12") (pinfunction "12_12") (pintype "passive"))
      (node (ref "U1") (pin "13") (pinfunction "GPIO9,_I/O/T_RTC_GPIO9,__TOUCH9,_ADC1_CH8,_FSPIHD,_SUBSPIHD_13") (pintype "passive"))
    )
    (net (code "33") (name "/GPIO10") (class "Default")
      (node (ref "J1") (pin "13") (pinfunction "13_13") (pintype "passive"))
      (node (ref "U1") (pin "14") (pinfunction "GPIO10,_RTC_GPIO10,__TOUCH10,_ADC1_CH9,_FSPICS0,_FSPIIO4,_SUBSPICS0_14") (pintype "passive"))
    )
    (net (code "34") (name "/GPIO11") (class "Default")
      (node (ref "J1") (pin "14") (pinfunction "14_14") (pintype "passive"))
      (node (ref "U1") (pin "15") (pinfunction "GPIO11,_RTC_GPIO11,__TOUCH11,_ADC2_CH0,_FSPID,_FSPIIO5,_SUBSPID_15") (pintype "passive"))
    )
    (net (code "35") (name "/GPIO12") (class "Default")
      (node (ref "J1") (pin "15") (pinfunction "15_15") (pintype "passive"))
      (node (ref "U1") (pin "16") (pinfunction "GPIO12,_RTC_GPIO12,__TOUCH12,_ADC2_CH1,_FSPICLK,_FSPIIO6,_SUBSPICLK_16") (pintype "passive"))
    )
    (net (code "36") (name "/GPIO13") (class "Default")
      (node (ref "J1") (pin "16") (pinfunction "16_16") (pintype "passive"))
      (node (ref "U1") (pin "17") (pinfunction "GPIO13,_RTC_GPIO13,__TOUCH13,_ADC2_CH2,_FSPIQ,_FSPIIO7,_SUBSPIQ_17") (pintype "passive"))
    )
    (net (code "37") (name "/GPIO14") (class "Default")
      (node (ref "J1") (pin "17") (pinfunction "17_17") (pintype "passive"))
      (node (ref "U1") (pin "18") (pinfunction "GPIO14,_RTC_GPIO14,__TOUCH14,_ADC2_CH3,_FSPIWP,_FSPIDQS,_SUBSPIWP_18") (pintype "passive"))
    )
    (net (code "38") (name "/GPIO15") (class "Default")
      (node (ref "J1") (pin "18") (pinfunction "18_18") (pintype "passive"))
      (node (ref "U1") (pin "19") (pinfunction "GPIO15,_I/O/T_RTC_GPIO15,__U0RTS,_ADC2_CH4,_XTAL_32K_P_19") (pintype "passive"))
    )
    (net (code "39") (name "/GPIO16") (class "Default")
      (node (ref "J1") (pin "19") (pinfunction "19_19") (pintype "passive"))
      (node (ref "U1") (pin "20") (pinfunction "GPIO16,_I/O/T_RTC_GPIO16,__U0CTS,_ADC2_CH5,_XTAL_32K_N_20") (pintype "passive"))
    )
    (net (code "40") (name "/GPIO17") (class "Default")
      (node (ref "J1") (pin "20") (pinfunction "20_20") (pintype "passive"))
      (node (ref "U1") (pin "21") (pinfunction "GPIO17,_I/O/T_RTC_GPIO17,__U1TXD,_ADC2_CH6_21") (pintype "passive"))
    )
    (net (code "41") (name "/GPIO18") (class "Default")
      (node (ref "J1") (pin "21") (pinfunction "21_21") (pintype "passive"))
      (node (ref "U1") (pin "22") (pinfunction "GPIO18,_I/O/T_RTC_GPIO18,__U1RXD,_ADC2_CH7,_CLK_OUT3_22") (pintype "passive"))
    )
    (net (code "42") (name "/GPIO21") (class "Default")
      (node (ref "J2") (pin "19") (pinfunction "19_19") (pintype "passive"))
      (node (ref "U1") (pin "25") (pinfunction "GPIO21,_I/O/T_RTC_GPIO21,_25") (pintype "passive"))
    )
    (net (code "43") (name "/GPIO26") (class "Default")
      (node (ref "J2") (pin "18") (pinfunction "18_18") (pintype "passive"))
      (node (ref "U1") (pin "26") (pinfunction "GPIO26,_I/O/T_SPICS1_26") (pintype "passive"))
    )
    (net (code "44") (name "/GPIO33") (class "Default")
      (node (ref "J2") (pin "17") (pinfunction "17_17") (pintype "passive"))
      (node (ref "U1") (pin "28") (pinfunction "GPIO33,_SPIIO4,__FSPIHD,_SUBSPIHD_28") (pintype "passive"))
    )
    (net (code "45") (name "/GPIO34") (class "Default")
      (node (ref "J2") (pin "16") (pinfunction "16_16") (pintype "passive"))
      (node (ref "U1") (pin "29") (pinfunction "GPIO34,_SPIIO5,__FSPICS0,_SUBSPICS0_29") (pintype "passive"))
    )
    (net (code "46") (name "/GPIO35") (class "Default")
      (node (ref "J2") (pin "15") (pinfunction "15_15") (pintype "passive"))
      (node (ref "U1") (pin "31") (pinfunction "GPIO35,_SPIIO6,__FSPID,_SUBSPID_31") (pintype "passive"))
    )
    (net (code "47") (name "/GPIO36") (class "Default")
      (node (ref "J2") (pin "14") (pinfunction "14_14") (pintype "passive"))
      (node (ref "U1") (pin "32") (pinfunction "GPIO36,_SPIIO7,__FSPICLK,_SUBSPICLK_32") (pintype "passive"))
    )
    (net (code "48") (name "/GPIO37") (class "Default")
      (node (ref "J2") (pin "13") (pinfunction "13_13") (pintype "passive"))
      (node (ref "U1") (pin "33") (pinfunction "GPIO37,_SPIDQS,__FSPIQ,_SUBSPIQ_33") (pintype "passive"))
    )
    (net (code "49") (name "/GPIO38") (class "Default")
      (node (ref "J2") (pin "12") (pinfunction "12_12") (pintype "passive"))
      (node (ref "U1") (pin "34") (pinfunction "GPIO38,_FSPIWP,_SUBSPIWP_34") (pintype "passive"))
    )
    (net (code "50") (name "/GPIO39") (class "Default")
      (node (ref "J2") (pin "11") (pinfunction "11_11") (pintype "passive"))
      (node (ref "U1") (pin "35") (pinfunction "GPIO39,_MTCK,_CLK_OUT3,_SUBSPICS1_35") (pintype "passive"))
    )
    (net (code "51") (name "/GPIO40") (class "Default")
      (node (ref "J2") (pin "10") (pinfunction "10_10") (pintype "passive"))
      (node (ref "U1") (pin "36") (pinfunction "GPIO40,_MTDO,__CLK_OUT2_36") (pintype "passive"))
    )
    (net (code "52") (name "/GPIO41") (class "Default")
      (node (ref "J2") (pin "9") (pinfunction "9_9") (pintype "passive"))
      (node (ref "U1") (pin "37") (pinfunction "GPIO41,_MTDI,__CLK_OUT1_37") (pintype "passive"))
    )
    (net (code "53") (name "/GPIO42") (class "Default")
      (node (ref "J2") (pin "8") (pinfunction "8_8") (pintype "passive"))
      (node (ref "U1") (pin "38") (pinfunction "GPIO42,_MTMS_38") (pintype "passive"))
    )
    (net (code "54") (name "/GPIO45") (class "Default")
      (node (ref "J2") (pin "5") (pinfunction "5_5") (pintype "passive"))
      (node (ref "U1") (pin "41") (pinfunction "GPIO45_41") (pintype "passive"))
    )
    (net (code "55") (name "/GPIO46") (class "Default")
      (node (ref "J2") (pin "4") (pinfunction "4_4") (pintype "passive"))
      (node (ref "U1") (pin "44") (pinfunction "GPIO46_44") (pintype "passive"))
    )
    (net (code "56") (name "/GPIO47") (class "Default")
      (node (ref "J2") (pin "23") (pinfunction "23_23") (pintype "passive"))
      (node (ref "U1") (pin "27") (pinfunction "GPIO47,_I/O/T_SPICLK_P_DIFF,__SUBSPICLK_P_DIFF_27") (pintype "passive"))
    )
    (net (code "57") (name "/GPIO48") (class "Default")
      (node (ref "J2") (pin "22") (pinfunction "22_22") (pintype "passive"))
      (node (ref "U1") (pin "30") (pinfunction "GPIO48,_SPICLK_N_DIFF,__SUBSPICLK_N_DIFF_30") (pintype "passive"))
    )
    (net (code "58") (name "/RTS_FTDI") (class "Default")
      (node (ref "Q1") (pin "2") (pinfunction "E_2") (pintype "passive"))
      (node (ref "R19") (pin "1") (pinfunction "1_1") (pintype "passive"))
      (node (ref "U3") (pin "19") (pinfunction "~{RTS}_19") (pintype "passive"))
    )
    (net (code "59") (name "/RXD_FTDI") (class "Default")
      (node (ref "R17") (pin "2") (pinfunction "2_2") (pintype "passive"))
      (node (ref "U3") (pin "1") (pinfunction "RXD_1") (pintype "passive"))
    )
    (net (code "60") (name "/TXD_FTDI") (class "Default")
      (node (ref "R18") (pin "2") (pinfunction "2_2") (pintype "passive"))
      (node (ref "U3") (pin "17") (pinfunction "TXD_17") (pintype "passive"))
    )
    (net (code "61") (name "/U0RXD") (class "Default")
      (node (ref "J2") (pin "6") (pinfunction "6_6") (pintype "passive"))
      (node (ref "R18") (pin "1") (pinfunction "1_1") (pintype "passive"))
      (node (ref "U1") (pin "40") (pinfunction "U0RXD,_GPIO44,_CLK_OUT2_40") (pintype "passive"))
    )
    (net (code "62") (name "/U0TXD") (class "Default")
      (node (ref "J2") (pin "7") (pinfunction "7_7") (pintype "passive"))
      (node (ref "R17") (pin "1") (pinfunction "1_1") (pintype "passive"))
      (node (ref "U1") (pin "39") (pinfunction "U0TXD,_GPIO43,_CLK_OUT1_39") (pintype "passive"))
    )
    (net (code "63") (name "/VBUS_SENSE") (class "Default")
      (node (ref "R12") (pin "1") (pinfunction "1_1") (pintype "passive"))
      (node (ref "R13") (pin "2") (pinfunction "2_2") (pintype "passive"))
      (node (ref "U3") (pin "16") (pinfunction "CBUS3_16") (pintype "passive"))
    )
    (net (code "64") (name "GND") (class "Default")
      (node (ref "C1") (pin "1") (pinfunction "1_1") (pintype "passive"))
      (node (ref "C10") (pin "1") (pinfunction "1_1") (pintype "passive"))
      (node (ref "C11") (pin "1") (pinfunction "1_1") (pintype "passive"))
      (node (ref "C12") (pin "1") (pinfunction "1_1") (pintype "passive"))
      (node (ref "C13") (pin "1") (pinfunction "1_1") (pintype "passive"))
      (node (ref "C14") (pin "1") (pinfunction "1_1") (pintype "passive"))
      (node (ref "C15") (pin "1") (pinfunction "1_1") (pintype "passive"))
      (node (ref "C16") (pin "1") (pinfunction "1_1") (pintype "passive"))
      (node (ref "C17") (pin "1") (pinfunction "1_1") (pintype "passive"))
      (node (ref "C2") (pin "1") (pinfunction "1_1") (pintype "passive"))
      (node (ref "C3") (pin "1") (pinfunction "1_1") (pintype "passive"))
      (node (ref "C4") (pin "1") (pinfunction "1_1") (pintype "passive"))
      (node (ref "C5") (pin "1") (pinfunction "1_1") (pintype "passive"))
      (node (ref "C6") (pin "1") (pinfunction "1_1") (pintype "passive"))
      (node (ref "C7") (pin "1") (pinfunction "1_1") (pintype "passive"))
      (node (ref "C8") (pin "1") (pinfunction "1_1") (pintype "passive"))
      (node (ref "C9") (pin "1") (pinfunction "1_1") (pintype "passive"))
      (node (ref "D1") (pin "1") (pinfunction "1_1") (pintype "passive"))
      (node (ref "D2") (pin "1") (pinfunction "1_1") (pintype "passive"))
      (node (ref "D3") (pin "1") (pinfunction "1_1") (pintype "passive"))
      (node (ref "D4") (pin "1") (pinfunction "1_1") (pintype "passive"))
      (node (ref "D5") (pin "1") (pinfunction "1_1") (pintype "passive"))
      (node (ref "D6") (pin "1") (pinfunction "1_1") (pintype "passive"))
      (node (ref "D7") (pin "K-") (pinfunction "2_K-") (pintype "passive"))
      (node (ref "J1") (pin "1") (pinfunction "1_1") (pintype "passive"))
      (node (ref "J1") (pin "23") (pinfunction "23_23") (pintype "passive"))
      (node (ref "J2") (pin "2") (pinfunction "2_2") (pintype "passive"))
      (node (ref "J3") (pin "A1B12") (pinfunction "GND_A1B12_A1B12") (pintype "passive"))
      (node (ref "J3") (pin "B1A12") (pinfunction "GND_B1A12_B1A12") (pintype "passive"))
      (node (ref "J3") (pin "S1") (pinfunction "SHIELD_1_S1") (pintype "passive"))
      (node (ref "J3") (pin "S2") (pinfunction "SHIELD_2_S2") (pintype "passive"))
      (node (ref "J3") (pin "S3") (pinfunction "SHIELD_3_S3") (pintype "passive"))
      (node (ref "J3") (pin "S4") (pinfunction "SHIELD_4_S4") (pintype "passive"))
      (node (ref "J4") (pin "A1B12") (pinfunction "GND_A1B12_A1B12") (pintype "passive"))
      (node (ref "J4") (pin "B1A12") (pinfunction "GND_B1A12_B1A12") (pintype "passive"))
      (node (ref "J4") (pin "S1") (pinfunction "SHIELD_1_S1") (pintype "passive"))
      (node (ref "J4") (pin "S2") (pinfunction "SHIELD_2_S2") (pintype "passive"))
      (node (ref "J4") (pin "S3") (pinfunction "SHIELD_3_S3") (pintype "passive"))
      (node (ref "J4") (pin "S4") (pinfunction "SHIELD_4_S4") (pintype "passive"))
      (node (ref "R1") (pin "2") (pinfunction "2_2") (pintype "passive"))
      (node (ref "R10") (pin "2") (pinfunction "2_2") (pintype "passive"))
      (node (ref "R11") (pin "2") (pinfunction "2_2") (pintype "passive"))
      (node (ref "R13") (pin "1") (pinfunction "1_1") (pintype "passive"))
      (node (ref "R2") (pin "2") (pinfunction "2_2") (pintype "passive"))
      (node (ref "R9") (pin "2") (pinfunction "2_2") (pintype "passive"))
      (node (ref "SW1") (pin "3") (pinfunction "3_3") (pintype "passive"))
      (node (ref "SW1") (pin "4") (pinfunction "4_4") (pintype "passive"))
      (node (ref "SW2") (pin "3") (pinfunction "3_3") (pintype "passive"))
      (node (ref "SW2") (pin "4") (pinfunction "4_4") (pintype "passive"))
      (node (ref "U1") (pin "1") (pinfunction "GND_1_1") (pintype "passive"))
      (node (ref "U1") (pin "2") (pinfunction "GND_2_2") (pintype "passive"))
      (node (ref "U1") (pin "42") (pinfunction "GND_3_42") (pintype "passive"))
      (node (ref "U1") (pin "43") (pinfunction "GND_4_43") (pintype "passive"))
      (node (ref "U1") (pin "46") (pinfunction "GND_46_46") (pintype "passive"))
      (node (ref "U1") (pin "47") (pinfunction "GND_47_47") (pintype "passive"))
      (node (ref "U1") (pin "48") (pinfunction "GND_48_48") (pintype "passive"))
      (node (ref "U1") (pin "49") (pinfunction "GND_49_49") (pintype "passive"))
      (node (ref "U1") (pin "50") (pinfunction "GND_50_50") (pintype "passive"))
      (node (ref "U1") (pin "51") (pinfunction "GND_51_51") (pintype "passive"))
      (node (ref "U1") (pin "52") (pinfunction "GND_52_52") (pintype "passive"))
      (node (ref "U1") (pin "53") (pinfunction "GND_53_53") (pintype "passive"))
      (node (ref "U1") (pin "54") (pinfunction "GND_54_54") (pintype "passive"))
      (node (ref "U1") (pin "55") (pinfunction "GND_55_55") (pintype "passive"))
      (node (ref "U1") (pin "56") (pinfunction "GND_56_56") (pintype "passive"))
      (node (ref "U1") (pin "57") (pinfunction "GND_57_57") (pintype "passive"))
      (node (ref "U1") (pin "58") (pinfunction "GND_58_58") (pintype "passive"))
      (node (ref "U1") (pin "59") (pinfunction "GND_59_59") (pintype "passive"))
      (node (ref "U1") (pin "60") (pinfunction "GND_60_60") (pintype "passive"))
      (node (ref "U1") (pin "61") (pinfunction "GND_61_61") (pintype "passive"))
      (node (ref "U1") (pin "62") (pinfunction "GND_62_62") (pintype "passive"))
      (node (ref "U1") (pin "63") (pinfunction "GND_63_63") (pintype "passive"))
      (node (ref "U1") (pin "64") (pinfunction "GND_64_64") (pintype "passive"))
      (node (ref "U1") (pin "65") (pinfunction "GND_65_65") (pintype "passive"))
      (node (ref "U1") (pin "66") (pinfunction "GND_66_66") (pintype "passive"))
      (node (ref "U1") (pin "67") (pinfunction "GND_67_67") (pintype "passive"))
      (node (ref "U1") (pin "68") (pinfunction "GND_68_68") (pintype "passive"))
      (node (ref "U1") (pin "69") (pinfunction "GND_69_69") (pintype "passive"))
      (node (ref "U1") (pin "70") (pinfunction "GND_70_70") (pintype "passive"))
      (node (ref "U1") (pin "71") (pinfunction "GND_71_71") (pintype "passive"))
      (node (ref "U1") (pin "72") (pinfunction "GND_72_72") (pintype "passive"))
      (node (ref "U1") (pin "73") (pinfunction "GND_73_73") (pintype "passive"))
      (node (ref "U2") (pin "2") (pinfunction "GND_2") (pintype "power_in"))
      (node (ref "U2") (pin "4") (pinfunction "GND_4") (pintype "power_in"))
      (node (ref "U3") (pin "13") (pinfunction "GND_13") (pintype "passive"))
      (node (ref "U3") (pin "21") (pinfunction "GND_21") (pintype "passive"))
      (node (ref "U3") (pin "3") (pinfunction "GND_3") (pintype "passive"))
    )
    (net (code "65") (name "Net-(D7-1)") (class "Default")
      (node (ref "D7") (pin "A+") (pinfunction "1_A+") (pintype "passive"))
      (node (ref "R24") (pin "2") (pinfunction "2_2") (pintype "passive"))
    )
    (net (code "66") (name "Net-(D8-1)") (class "Default")
      (node (ref "D8") (pin "A+") (pinfunction "1_A+") (pintype "passive"))
      (node (ref "R25") (pin "2") (pinfunction "2_2") (pintype "passive"))
    )
    (net (code "67") (name "Net-(J3-CC1)") (class "Default")
      (node (ref "J3") (pin "A5") (pinfunction "CC1_A5") (pintype "passive"))
      (node (ref "R2") (pin "1") (pinfunction "1_1") (pintype "passive"))
    )
    (net (code "68") (name "Net-(J3-CC2)") (class "Default")
      (node (ref "J3") (pin "B5") (pinfunction "CC2_B5") (pintype "passive"))
      (node (ref "R1") (pin "1") (pinfunction "1_1") (pintype "passive"))
    )
    (net (code "69") (name "Net-(J4-CC1)") (class "Default")
      (node (ref "J4") (pin "A5") (pinfunction "CC1_A5") (pintype "passive"))
      (node (ref "R11") (pin "1") (pinfunction "1_1") (pintype "passive"))
    )
    (net (code "70") (name "Net-(J4-CC2)") (class "Default")
      (node (ref "J4") (pin "B5") (pinfunction "CC2_B5") (pintype "passive"))
      (node (ref "R10") (pin "1") (pinfunction "1_1") (pintype "passive"))
    )
    (net (code "71") (name "Net-(Q1-B)") (class "Default")
      (node (ref "Q1") (pin "1") (pinfunction "B_1") (pintype "passive"))
      (node (ref "R15") (pin "2") (pinfunction "2_2") (pintype "passive"))
    )
    (net (code "72") (name "Net-(Q2-B)") (class "Default")
      (node (ref "Q2") (pin "1") (pinfunction "B_1") (pintype "passive"))
      (node (ref "R19") (pin "2") (pinfunction "2_2") (pintype "passive"))
    )
    (net (code "73") (name "Net-(U3-CBUS0)") (class "Default")
      (node (ref "R9") (pin "1") (pinfunction "1_1") (pintype "passive"))
      (node (ref "U3") (pin "15") (pinfunction "CBUS0_15") (pintype "passive"))
    )
    (net (code "74") (name "unconnected-(J1-Pad24)") (class "Default")
      (node (ref "J1") (pin "24") (pinfunction "24_24") (pintype "passive+no_connect"))
    )
    (net (code "75") (name "unconnected-(J2-Pad24)") (class "Default")
      (node (ref "J2") (pin "24") (pinfunction "24_24") (pintype "passive"))
    )
    (net (code "76") (name "unconnected-(J3-SBU1-PadA8)") (class "Default")
      (node (ref "J3") (pin "A8") (pinfunction "SBU1_A8") (pintype "passive+no_connect"))
    )
    (net (code "77") (name "unconnected-(J3-SBU2-PadB8)") (class "Default")
      (node (ref "J3") (pin "B8") (pinfunction "SBU2_B8") (pintype "passive+no_connect"))
    )
    (net (code "78") (name "unconnected-(J4-SBU1-PadA8)") (class "Default")
      (node (ref "J4") (pin "A8") (pinfunction "SBU1_A8") (pintype "passive+no_connect"))
    )
    (net (code "79") (name "unconnected-(J4-SBU2-PadB8)") (class "Default")
      (node (ref "J4") (pin "B8") (pinfunction "SBU2_B8") (pintype "passive+no_connect"))
    )
    (net (code "80") (name "unconnected-(U3-CBUS1-Pad14)") (class "Default")
      (node (ref "U3") (pin "14") (pinfunction "CBUS1_14") (pintype "passive+no_connect"))
    )
    (net (code "81") (name "unconnected-(U3-CBUS2-Pad7)") (class "Default")
      (node (ref "U3") (pin "7") (pinfunction "CBUS2_7") (pintype "passive+no_connect"))
    )
    (net (code "82") (name "unconnected-(U3-~{CTS}-Pad6)") (class "Default")
      (node (ref "U3") (pin "6") (pinfunction "~{CTS}_6") (pintype "passive"))
    )
    (net (code "83") (name "unconnected-(U3-~{DCD}-Pad5)") (class "Default")
      (node (ref "U3") (pin "5") (pinfunction "~{DCD}_5") (pintype "passive"))
    )
    (net (code "84") (name "unconnected-(U3-~{DSR}-Pad4)") (class "Default")
      (node (ref "U3") (pin "4") (pinfunction "~{DSR}_4") (pintype "passive"))
    )
    (net (code "85") (name "unconnected-(U3-~{RI}-Pad2)") (class "Default")
      (node (ref "U3") (pin "2") (pinfunction "~{RI}_2") (pintype "passive"))
    )
  )
)
